# 04_-OUTPUT.net
KiCad netlist of a schematic drawn in Altium Designer
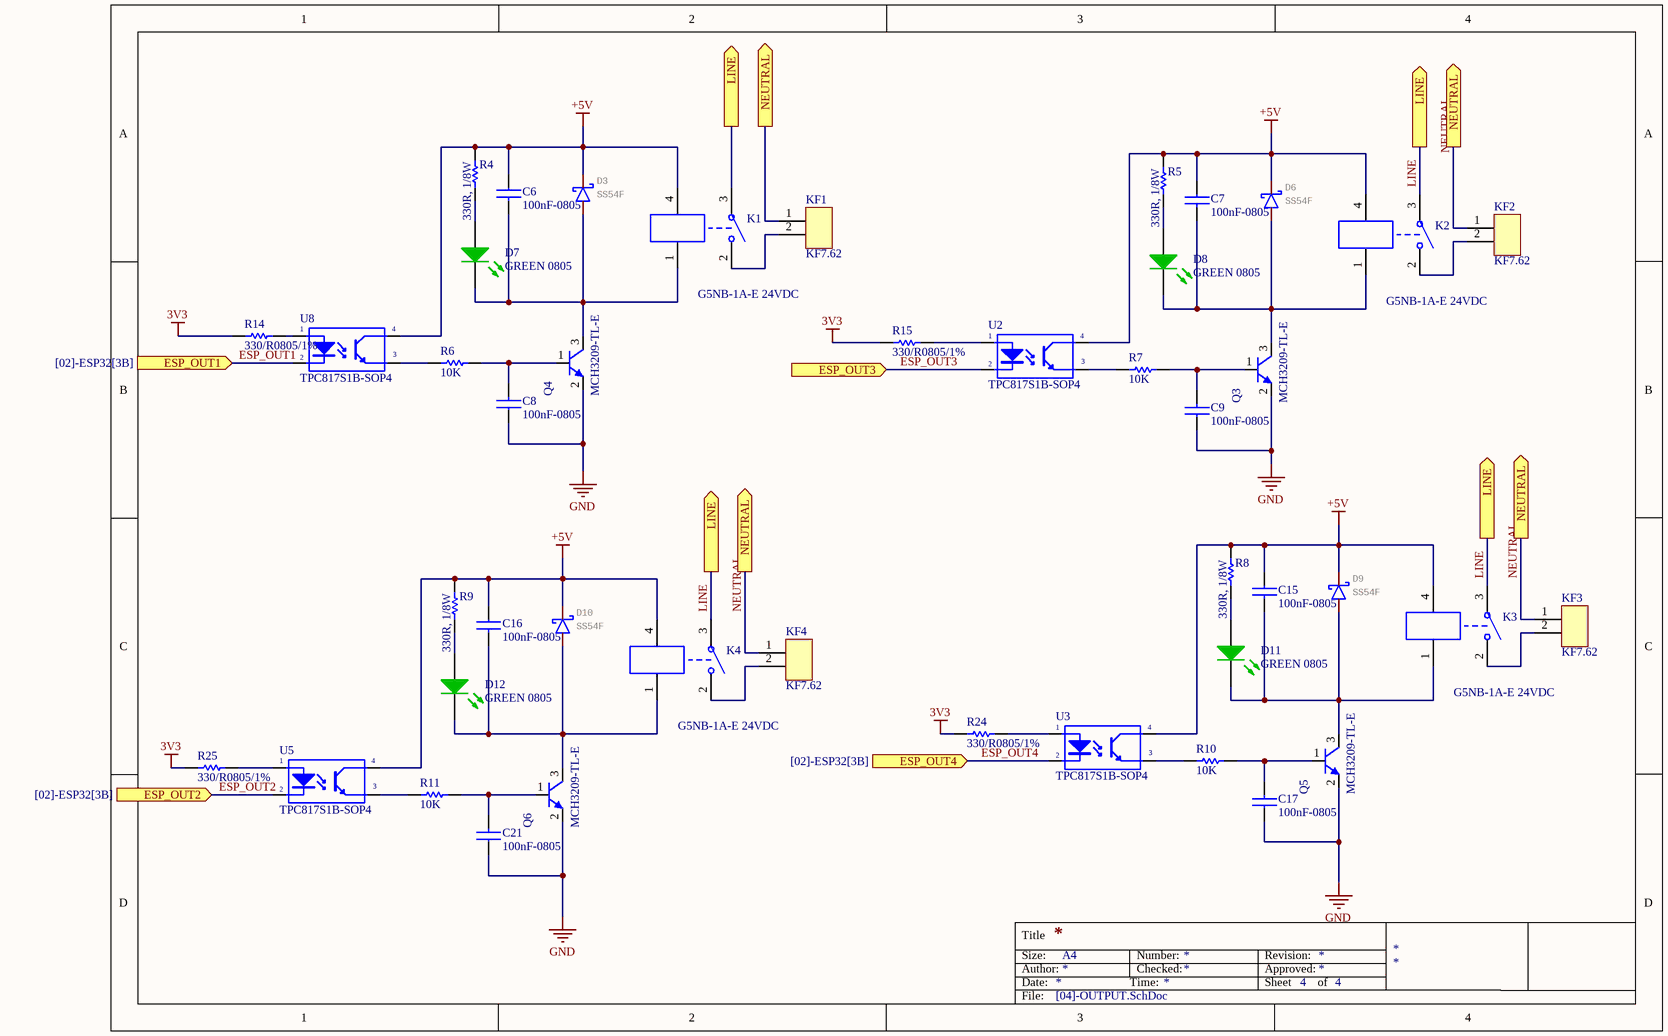
[diagram p0: [04]-OUTPUT.SchDoc]

(export (version "E")
  (design (tool "Eeschema 10.0.6"))
  (components
    (comp (ref "C6")
      (value "100nF-0805")
      (footprint "CAP0805")
      (description "CAP CER 0.1UF 50V X7R 0805")
      (fields
        (field (name "MANUFACTURER") "Yageo")
        (field (name "MANUFACTURER PART NUMBER") "CC0805KRX7R9BB104")
      )
      (libsource (lib "Indruino") (part "CC0805KRX7R9BB104"))
    )
    (comp (ref "C7")
      (value "100nF-0805")
      (footprint "CAP0805")
      (description "CAP CER 0.1UF 50V X7R 0805")
      (fields
        (field (name "MANUFACTURER") "Yageo")
        (field (name "MANUFACTURER PART NUMBER") "CC0805KRX7R9BB104")
      )
      (libsource (lib "Indruino") (part "CC0805KRX7R9BB104"))
    )
    (comp (ref "C8")
      (value "100nF-0805")
      (footprint "CAP0805")
      (description "CAP CER 0.1UF 50V X7R 0805")
      (fields
        (field (name "MANUFACTURER") "Yageo")
        (field (name "MANUFACTURER PART NUMBER") "CC0805KRX7R9BB104")
      )
      (libsource (lib "Indruino") (part "CC0805KRX7R9BB104"))
    )
    (comp (ref "C9")
      (value "100nF-0805")
      (footprint "CAP0805")
      (description "CAP CER 0.1UF 50V X7R 0805")
      (fields
        (field (name "MANUFACTURER") "Yageo")
        (field (name "MANUFACTURER PART NUMBER") "CC0805KRX7R9BB104")
      )
      (libsource (lib "Indruino") (part "CC0805KRX7R9BB104"))
    )
    (comp (ref "C15")
      (value "100nF-0805")
      (footprint "CAP0805")
      (description "CAP CER 0.1UF 50V X7R 0805")
      (fields
        (field (name "MANUFACTURER") "Yageo")
        (field (name "MANUFACTURER PART NUMBER") "CC0805KRX7R9BB104")
      )
      (libsource (lib "Indruino") (part "CC0805KRX7R9BB104"))
    )
    (comp (ref "C16")
      (value "100nF-0805")
      (footprint "CAP0805")
      (description "CAP CER 0.1UF 50V X7R 0805")
      (fields
        (field (name "MANUFACTURER") "Yageo")
        (field (name "MANUFACTURER PART NUMBER") "CC0805KRX7R9BB104")
      )
      (libsource (lib "Indruino") (part "CC0805KRX7R9BB104"))
    )
    (comp (ref "C17")
      (value "100nF-0805")
      (footprint "CAP0805")
      (description "CAP CER 0.1UF 50V X7R 0805")
      (fields
        (field (name "MANUFACTURER") "Yageo")
        (field (name "MANUFACTURER PART NUMBER") "CC0805KRX7R9BB104")
      )
      (libsource (lib "Indruino") (part "CC0805KRX7R9BB104"))
    )
    (comp (ref "C21")
      (value "100nF-0805")
      (footprint "CAP0805")
      (description "CAP CER 0.1UF 50V X7R 0805")
      (fields
        (field (name "MANUFACTURER") "Yageo")
        (field (name "MANUFACTURER PART NUMBER") "CC0805KRX7R9BB104")
      )
      (libsource (lib "Indruino") (part "CC0805KRX7R9BB104"))
    )
    (comp (ref "D3") (value "SS54F") (footprint "SMAF") (libsource (lib "UY_Schlib") (part "SS54F")))
    (comp (ref "D6") (value "SS54F") (footprint "SMAF") (libsource (lib "UY_Schlib") (part "SS54F")))
    (comp (ref "D7")
      (value "GREEN 0805")
      (footprint "Led 0805G")
      (description "Green 571nm LED Indication - Discrete 2V 0805 (2012 Metric)")
      (libsource (lib "Mach o cam dien thong minh") (part "LED GREEN 0603"))
    )
    (comp (ref "D8")
      (value "GREEN 0805")
      (footprint "Led 0805G")
      (description "Green 571nm LED Indication - Discrete 2V 0805 (2012 Metric)")
      (libsource (lib "Mach o cam dien thong minh") (part "LED GREEN 0603"))
    )
    (comp (ref "D9") (value "SS54F") (footprint "SMAF") (libsource (lib "UY_Schlib") (part "SS54F")))
    (comp (ref "D10") (value "SS54F") (footprint "SMAF") (libsource (lib "UY_Schlib") (part "SS54F")))
    (comp (ref "D11")
      (value "GREEN 0805")
      (footprint "Led 0805G")
      (description "Green 571nm LED Indication - Discrete 2V 0805 (2012 Metric)")
      (libsource (lib "Mach o cam dien thong minh") (part "LED GREEN 0603"))
    )
    (comp (ref "D12")
      (value "GREEN 0805")
      (footprint "Led 0805G")
      (description "Green 571nm LED Indication - Discrete 2V 0805 (2012 Metric)")
      (libsource (lib "Mach o cam dien thong minh") (part "LED GREEN 0603"))
    )
    (comp (ref "K1")
      (value "G5NB-1A-E 24VDC")
      (footprint "MinhTien_PCBLib:RELAY-G5NB-1A-E 24VDC")
      (description "Relay 24VDC SPST-NO General Purpose / Industrial")
      (fields (field (name "PUBLISHER") "Altium Limited"))
      (libsource (lib "MinhTien_SCHLib") (part "Relay-G5NB-1A-E 24VDC"))
    )
    (comp (ref "K2")
      (value "G5NB-1A-E 24VDC")
      (footprint "MinhTien_PCBLib:RELAY-G5NB-1A-E 24VDC")
      (description "Relay 24VDC SPST-NO General Purpose / Industrial")
      (fields (field (name "PUBLISHER") "Altium Limited"))
      (libsource (lib "MinhTien_SCHLib") (part "Relay-G5NB-1A-E 24VDC"))
    )
    (comp (ref "K3")
      (value "G5NB-1A-E 24VDC")
      (footprint "MinhTien_PCBLib:RELAY-G5NB-1A-E 24VDC")
      (description "Relay 24VDC SPST-NO General Purpose / Industrial")
      (fields (field (name "PUBLISHER") "Altium Limited"))
      (libsource (lib "MinhTien_SCHLib") (part "Relay-G5NB-1A-E 24VDC"))
    )
    (comp (ref "K4")
      (value "G5NB-1A-E 24VDC")
      (footprint "MinhTien_PCBLib:RELAY-G5NB-1A-E 24VDC")
      (description "Relay 24VDC SPST-NO General Purpose / Industrial")
      (fields (field (name "PUBLISHER") "Altium Limited"))
      (libsource (lib "MinhTien_SCHLib") (part "Relay-G5NB-1A-E 24VDC"))
    )
    (comp (ref "KF1")
      (value "KF7.62")
      (footprint "LPSON_CON:KF-7.62")
      (libsource (lib "lpson") (part "KF 2P"))
    )
    (comp (ref "KF2")
      (value "KF7.62")
      (footprint "LPSON_CON:KF-7.62")
      (libsource (lib "lpson") (part "KF 2P"))
    )
    (comp (ref "KF3")
      (value "KF7.62")
      (footprint "LPSON_CON:KF-7.62")
      (libsource (lib "lpson") (part "KF 2P"))
    )
    (comp (ref "KF4")
      (value "KF7.62")
      (footprint "LPSON_CON:KF-7.62")
      (libsource (lib "lpson") (part "KF 2P"))
    )
    (comp (ref "Q3")
      (value "MCH3209-TL-E")
      (footprint "MCH3209-TL-E  SOT-323")
      (description "Bipolar (BJT) Transistor NPN 30V 3A 450MHz 800mW Surface Mount 3-MCPH")
      (libsource (lib "Mach o cam dien thong minh") (part "2SC1815"))
    )
    (comp (ref "Q4")
      (value "MCH3209-TL-E")
      (footprint "MCH3209-TL-E  SOT-323")
      (description "Bipolar (BJT) Transistor NPN 30V 3A 450MHz 800mW Surface Mount 3-MCPH")
      (libsource (lib "Mach o cam dien thong minh") (part "2SC1815"))
    )
    (comp (ref "Q5")
      (value "MCH3209-TL-E")
      (footprint "MCH3209-TL-E  SOT-323")
      (description "Bipolar (BJT) Transistor NPN 30V 3A 450MHz 800mW Surface Mount 3-MCPH")
      (libsource (lib "Mach o cam dien thong minh") (part "2SC1815"))
    )
    (comp (ref "Q6")
      (value "MCH3209-TL-E")
      (footprint "MCH3209-TL-E  SOT-323")
      (description "Bipolar (BJT) Transistor NPN 30V 3A 450MHz 800mW Surface Mount 3-MCPH")
      (libsource (lib "Mach o cam dien thong minh") (part "2SC1815"))
    )
    (comp (ref "R4")
      (value "330R, 1/8W")
      (footprint "RESC2012L")
      (description "RES CR 0805 5% 1/8W 330R")
      (fields (field (name "Comment") "CR05JL7-330R"))
      (libsource (lib "lpson") (part "CR05JL7-330R"))
    )
    (comp (ref "R5")
      (value "330R, 1/8W")
      (footprint "RESC2012L")
      (description "RES CR 0805 5% 1/8W 330R")
      (fields (field (name "Comment") "CR05JL7-330R"))
      (libsource (lib "lpson") (part "CR05JL7-330R"))
    )
    (comp (ref "R6")
      (value "10K")
      (footprint "Res 0805 SMD")
      (description "RES SMD 249K OHM 1% 1/10W 0805")
      (fields
        (field (name "MANUFACTURER") "Yageo")
        (field (name "MANUFACTURER PART NUMBER") "RC0603FR-07249KL")
      )
      (libsource (lib "Mach o cam dien thong minh") (part "249K/R0805/1%"))
    )
    (comp (ref "R7")
      (value "10K")
      (footprint "Res 0805 SMD")
      (description "RES SMD 249K OHM 1% 1/10W 0805")
      (fields
        (field (name "MANUFACTURER") "Yageo")
        (field (name "MANUFACTURER PART NUMBER") "RC0603FR-07249KL")
      )
      (libsource (lib "Mach o cam dien thong minh") (part "249K/R0805/1%"))
    )
    (comp (ref "R8")
      (value "330R, 1/8W")
      (footprint "RESC2012L")
      (description "RES CR 0805 5% 1/8W 330R")
      (fields (field (name "Comment") "CR05JL7-330R"))
      (libsource (lib "lpson") (part "CR05JL7-330R"))
    )
    (comp (ref "R9")
      (value "330R, 1/8W")
      (footprint "RESC2012L")
      (description "RES CR 0805 5% 1/8W 330R")
      (fields (field (name "Comment") "CR05JL7-330R"))
      (libsource (lib "lpson") (part "CR05JL7-330R"))
    )
    (comp (ref "R10")
      (value "10K")
      (footprint "Res 0805 SMD")
      (description "RES SMD 249K OHM 1% 1/10W 0805")
      (fields
        (field (name "MANUFACTURER") "Yageo")
        (field (name "MANUFACTURER PART NUMBER") "RC0603FR-07249KL")
      )
      (libsource (lib "Mach o cam dien thong minh") (part "249K/R0805/1%"))
    )
    (comp (ref "R11")
      (value "10K")
      (footprint "Res 0805 SMD")
      (description "RES SMD 249K OHM 1% 1/10W 0805")
      (fields
        (field (name "MANUFACTURER") "Yageo")
        (field (name "MANUFACTURER PART NUMBER") "RC0603FR-07249KL")
      )
      (libsource (lib "Mach o cam dien thong minh") (part "249K/R0805/1%"))
    )
    (comp (ref "R14")
      (value "330/R0805/1%")
      (footprint "Res 0805 SMD")
      (description "RES SMD 249K OHM 1% 1/10W 0805")
      (fields
        (field (name "MANUFACTURER") "Yageo")
        (field (name "MANUFACTURER PART NUMBER") "RC0603FR-07249KL")
      )
      (libsource (lib "lpson") (part "249K/R0805/1%"))
    )
    (comp (ref "R15")
      (value "330/R0805/1%")
      (footprint "Res 0805 SMD")
      (description "RES SMD 249K OHM 1% 1/10W 0805")
      (fields
        (field (name "MANUFACTURER") "Yageo")
        (field (name "MANUFACTURER PART NUMBER") "RC0603FR-07249KL")
      )
      (libsource (lib "lpson") (part "249K/R0805/1%"))
    )
    (comp (ref "R24")
      (value "330/R0805/1%")
      (footprint "Res 0805 SMD")
      (description "RES SMD 249K OHM 1% 1/10W 0805")
      (fields
        (field (name "MANUFACTURER") "Yageo")
        (field (name "MANUFACTURER PART NUMBER") "RC0603FR-07249KL")
      )
      (libsource (lib "lpson") (part "249K/R0805/1%"))
    )
    (comp (ref "R25")
      (value "330/R0805/1%")
      (footprint "Res 0805 SMD")
      (description "RES SMD 249K OHM 1% 1/10W 0805")
      (fields
        (field (name "MANUFACTURER") "Yageo")
        (field (name "MANUFACTURER PART NUMBER") "RC0603FR-07249KL")
      )
      (libsource (lib "lpson") (part "249K/R0805/1%"))
    )
    (comp (ref "U2")
      (value "TPC817S1B-SOP4")
      (footprint "TPC817-4SOP")
      (description "Optoisolator Transistor Output 5000Vrms 1 Channel 4-SOP")
      (libsource (lib "Mach o cam dien thong minh") (part "PC817"))
    )
    (comp (ref "U3")
      (value "TPC817S1B-SOP4")
      (footprint "TPC817-4SOP")
      (description "Optoisolator Transistor Output 5000Vrms 1 Channel 4-SOP")
      (libsource (lib "Mach o cam dien thong minh") (part "PC817"))
    )
    (comp (ref "U5")
      (value "TPC817S1B-SOP4")
      (footprint "TPC817-4SOP")
      (description "Optoisolator Transistor Output 5000Vrms 1 Channel 4-SOP")
      (libsource (lib "Mach o cam dien thong minh") (part "PC817"))
    )
    (comp (ref "U8")
      (value "TPC817S1B-SOP4")
      (footprint "TPC817-4SOP")
      (description "Optoisolator Transistor Output 5000Vrms 1 Channel 4-SOP")
      (libsource (lib "Mach o cam dien thong minh") (part "PC817"))
    )
  )
  (nets
    (net (code "1") (name "+5V") (class "Default")
      (node (ref "C15") (pin "1") (pinfunction "1_1") (pintype "passive"))
      (node (ref "C16") (pin "1") (pinfunction "1_1") (pintype "passive"))
      (node (ref "C6") (pin "1") (pinfunction "1_1") (pintype "passive"))
      (node (ref "C7") (pin "1") (pinfunction "1_1") (pintype "passive"))
      (node (ref "D10") (pin "C") (pinfunction "C_C") (pintype "passive"))
      (node (ref "D3") (pin "C") (pinfunction "C_C") (pintype "passive"))
      (node (ref "D6") (pin "C") (pinfunction "C_C") (pintype "passive"))
      (node (ref "D9") (pin "C") (pinfunction "C_C") (pintype "passive"))
      (node (ref "K1") (pin "4") (pintype "passive"))
      (node (ref "K2") (pin "4") (pintype "passive"))
      (node (ref "K3") (pin "4") (pintype "passive"))
      (node (ref "K4") (pin "4") (pintype "passive"))
      (node (ref "R4") (pin "2") (pinfunction "2_2") (pintype "passive"))
      (node (ref "R5") (pin "2") (pinfunction "2_2") (pintype "passive"))
      (node (ref "R8") (pin "2") (pinfunction "2_2") (pintype "passive"))
      (node (ref "R9") (pin "2") (pinfunction "2_2") (pintype "passive"))
      (node (ref "U2") (pin "4") (pinfunction "C_4") (pintype "passive"))
      (node (ref "U3") (pin "4") (pinfunction "C_4") (pintype "passive"))
      (node (ref "U5") (pin "4") (pinfunction "C_4") (pintype "passive"))
      (node (ref "U8") (pin "4") (pinfunction "C_4") (pintype "passive"))
    )
    (net (code "2") (name "/ESP_OUT1") (class "Default")
      (node (ref "U8") (pin "2") (pinfunction "K_2") (pintype "passive"))
    )
    (net (code "3") (name "/ESP_OUT2") (class "Default")
      (node (ref "U5") (pin "2") (pinfunction "K_2") (pintype "passive"))
    )
    (net (code "4") (name "/ESP_OUT3") (class "Default")
      (node (ref "U2") (pin "2") (pinfunction "K_2") (pintype "passive"))
    )
    (net (code "5") (name "/ESP_OUT4") (class "Default")
      (node (ref "U3") (pin "2") (pinfunction "K_2") (pintype "passive"))
    )
    (net (code "6") (name "/LINE") (class "Default")
      (node (ref "K1") (pin "3") (pinfunction "NO_3") (pintype "passive"))
      (node (ref "K2") (pin "3") (pinfunction "NO_3") (pintype "passive"))
      (node (ref "K3") (pin "3") (pinfunction "NO_3") (pintype "passive"))
      (node (ref "K4") (pin "3") (pinfunction "NO_3") (pintype "passive"))
    )
    (net (code "7") (name "/NEUTRAL") (class "Default")
      (node (ref "KF1") (pin "1") (pinfunction "1_1") (pintype "passive"))
      (node (ref "KF2") (pin "1") (pinfunction "1_1") (pintype "passive"))
      (node (ref "KF3") (pin "1") (pinfunction "1_1") (pintype "passive"))
      (node (ref "KF4") (pin "1") (pinfunction "1_1") (pintype "passive"))
    )
    (net (code "8") (name "3V3") (class "Default")
      (node (ref "R14") (pin "1") (pinfunction "1_1") (pintype "passive"))
      (node (ref "R15") (pin "1") (pinfunction "1_1") (pintype "passive"))
      (node (ref "R24") (pin "1") (pinfunction "1_1") (pintype "passive"))
      (node (ref "R25") (pin "1") (pinfunction "1_1") (pintype "passive"))
    )
    (net (code "9") (name "GND") (class "Default")
      (node (ref "C17") (pin "1") (pinfunction "1_1") (pintype "passive"))
      (node (ref "C21") (pin "1") (pinfunction "1_1") (pintype "passive"))
      (node (ref "C8") (pin "1") (pinfunction "1_1") (pintype "passive"))
      (node (ref "C9") (pin "1") (pinfunction "1_1") (pintype "passive"))
      (node (ref "Q3") (pin "2") (pinfunction "E_2") (pintype "passive"))
      (node (ref "Q4") (pin "2") (pinfunction "E_2") (pintype "passive"))
      (node (ref "Q5") (pin "2") (pinfunction "E_2") (pintype "passive"))
      (node (ref "Q6") (pin "2") (pinfunction "E_2") (pintype "passive"))
    )
    (net (code "10") (name "Net-(D7-A)") (class "Default")
      (node (ref "D7") (pin "1") (pinfunction "A_1") (pintype "passive"))
      (node (ref "R4") (pin "1") (pinfunction "1_1") (pintype "passive"))
    )
    (net (code "11") (name "Net-(D7-K)") (class "Default")
      (node (ref "C6") (pin "2") (pinfunction "2_2") (pintype "passive"))
      (node (ref "D3") (pin "A") (pinfunction "A_A") (pintype "passive"))
      (node (ref "D7") (pin "2") (pinfunction "K_2") (pintype "passive"))
      (node (ref "K1") (pin "1") (pinfunction "COM_1") (pintype "passive"))
      (node (ref "Q4") (pin "3") (pinfunction "C_3") (pintype "passive"))
    )
    (net (code "12") (name "Net-(D8-A)") (class "Default")
      (node (ref "D8") (pin "1") (pinfunction "A_1") (pintype "passive"))
      (node (ref "R5") (pin "1") (pinfunction "1_1") (pintype "passive"))
    )
    (net (code "13") (name "Net-(D8-K)") (class "Default")
      (node (ref "C7") (pin "2") (pinfunction "2_2") (pintype "passive"))
      (node (ref "D6") (pin "A") (pinfunction "A_A") (pintype "passive"))
      (node (ref "D8") (pin "2") (pinfunction "K_2") (pintype "passive"))
      (node (ref "K2") (pin "1") (pinfunction "COM_1") (pintype "passive"))
      (node (ref "Q3") (pin "3") (pinfunction "C_3") (pintype "passive"))
    )
    (net (code "14") (name "Net-(D11-A)") (class "Default")
      (node (ref "D11") (pin "1") (pinfunction "A_1") (pintype "passive"))
      (node (ref "R8") (pin "1") (pinfunction "1_1") (pintype "passive"))
    )
    (net (code "15") (name "Net-(D11-K)") (class "Default")
      (node (ref "C15") (pin "2") (pinfunction "2_2") (pintype "passive"))
      (node (ref "D11") (pin "2") (pinfunction "K_2") (pintype "passive"))
      (node (ref "D9") (pin "A") (pinfunction "A_A") (pintype "passive"))
      (node (ref "K3") (pin "1") (pinfunction "COM_1") (pintype "passive"))
      (node (ref "Q5") (pin "3") (pinfunction "C_3") (pintype "passive"))
    )
    (net (code "16") (name "Net-(D12-A)") (class "Default")
      (node (ref "D12") (pin "1") (pinfunction "A_1") (pintype "passive"))
      (node (ref "R9") (pin "1") (pinfunction "1_1") (pintype "passive"))
    )
    (net (code "17") (name "Net-(D12-K)") (class "Default")
      (node (ref "C16") (pin "2") (pinfunction "2_2") (pintype "passive"))
      (node (ref "D10") (pin "A") (pinfunction "A_A") (pintype "passive"))
      (node (ref "D12") (pin "2") (pinfunction "K_2") (pintype "passive"))
      (node (ref "K4") (pin "1") (pinfunction "COM_1") (pintype "passive"))
      (node (ref "Q6") (pin "3") (pinfunction "C_3") (pintype "passive"))
    )
    (net (code "18") (name "Net-(K1-NC)") (class "Default")
      (node (ref "K1") (pin "2") (pinfunction "NC_2") (pintype "passive"))
      (node (ref "KF1") (pin "2") (pinfunction "2_2") (pintype "passive"))
    )
    (net (code "19") (name "Net-(K2-NC)") (class "Default")
      (node (ref "K2") (pin "2") (pinfunction "NC_2") (pintype "passive"))
      (node (ref "KF2") (pin "2") (pinfunction "2_2") (pintype "passive"))
    )
    (net (code "20") (name "Net-(K3-NC)") (class "Default")
      (node (ref "K3") (pin "2") (pinfunction "NC_2") (pintype "passive"))
      (node (ref "KF3") (pin "2") (pinfunction "2_2") (pintype "passive"))
    )
    (net (code "21") (name "Net-(K4-NC)") (class "Default")
      (node (ref "K4") (pin "2") (pinfunction "NC_2") (pintype "passive"))
      (node (ref "KF4") (pin "2") (pinfunction "2_2") (pintype "passive"))
    )
    (net (code "22") (name "Net-(Q3-B)") (class "Default")
      (node (ref "C9") (pin "2") (pinfunction "2_2") (pintype "passive"))
      (node (ref "Q3") (pin "1") (pinfunction "B_1") (pintype "passive"))
      (node (ref "R7") (pin "1") (pinfunction "1_1") (pintype "passive"))
    )
    (net (code "23") (name "Net-(Q4-B)") (class "Default")
      (node (ref "C8") (pin "2") (pinfunction "2_2") (pintype "passive"))
      (node (ref "Q4") (pin "1") (pinfunction "B_1") (pintype "passive"))
      (node (ref "R6") (pin "1") (pinfunction "1_1") (pintype "passive"))
    )
    (net (code "24") (name "Net-(Q5-B)") (class "Default")
      (node (ref "C17") (pin "2") (pinfunction "2_2") (pintype "passive"))
      (node (ref "Q5") (pin "1") (pinfunction "B_1") (pintype "passive"))
      (node (ref "R10") (pin "1") (pinfunction "1_1") (pintype "passive"))
    )
    (net (code "25") (name "Net-(Q6-B)") (class "Default")
      (node (ref "C21") (pin "2") (pinfunction "2_2") (pintype "passive"))
      (node (ref "Q6") (pin "1") (pinfunction "B_1") (pintype "passive"))
      (node (ref "R11") (pin "1") (pinfunction "1_1") (pintype "passive"))
    )
    (net (code "26") (name "Net-(U2-A)") (class "Default")
      (node (ref "R15") (pin "2") (pinfunction "2_2") (pintype "passive"))
      (node (ref "U2") (pin "1") (pinfunction "A_1") (pintype "passive"))
    )
    (net (code "27") (name "Net-(U2-E)") (class "Default")
      (node (ref "R7") (pin "2") (pinfunction "2_2") (pintype "passive"))
      (node (ref "U2") (pin "3") (pinfunction "E_3") (pintype "passive"))
    )
    (net (code "28") (name "Net-(U3-A)") (class "Default")
      (node (ref "R24") (pin "2") (pinfunction "2_2") (pintype "passive"))
      (node (ref "U3") (pin "1") (pinfunction "A_1") (pintype "passive"))
    )
    (net (code "29") (name "Net-(U3-E)") (class "Default")
      (node (ref "R10") (pin "2") (pinfunction "2_2") (pintype "passive"))
      (node (ref "U3") (pin "3") (pinfunction "E_3") (pintype "passive"))
    )
    (net (code "30") (name "Net-(U5-A)") (class "Default")
      (node (ref "R25") (pin "2") (pinfunction "2_2") (pintype "passive"))
      (node (ref "U5") (pin "1") (pinfunction "A_1") (pintype "passive"))
    )
    (net (code "31") (name "Net-(U5-E)") (class "Default")
      (node (ref "R11") (pin "2") (pinfunction "2_2") (pintype "passive"))
      (node (ref "U5") (pin "3") (pinfunction "E_3") (pintype "passive"))
    )
    (net (code "32") (name "Net-(U8-A)") (class "Default")
      (node (ref "R14") (pin "2") (pinfunction "2_2") (pintype "passive"))
      (node (ref "U8") (pin "1") (pinfunction "A_1") (pintype "passive"))
    )
    (net (code "33") (name "Net-(U8-E)") (class "Default")
      (node (ref "R6") (pin "2") (pinfunction "2_2") (pintype "passive"))
      (node (ref "U8") (pin "3") (pinfunction "E_3") (pintype "passive"))
    )
  )
)
